# main.net
KiCad netlist of a schematic drawn in Altium Designer
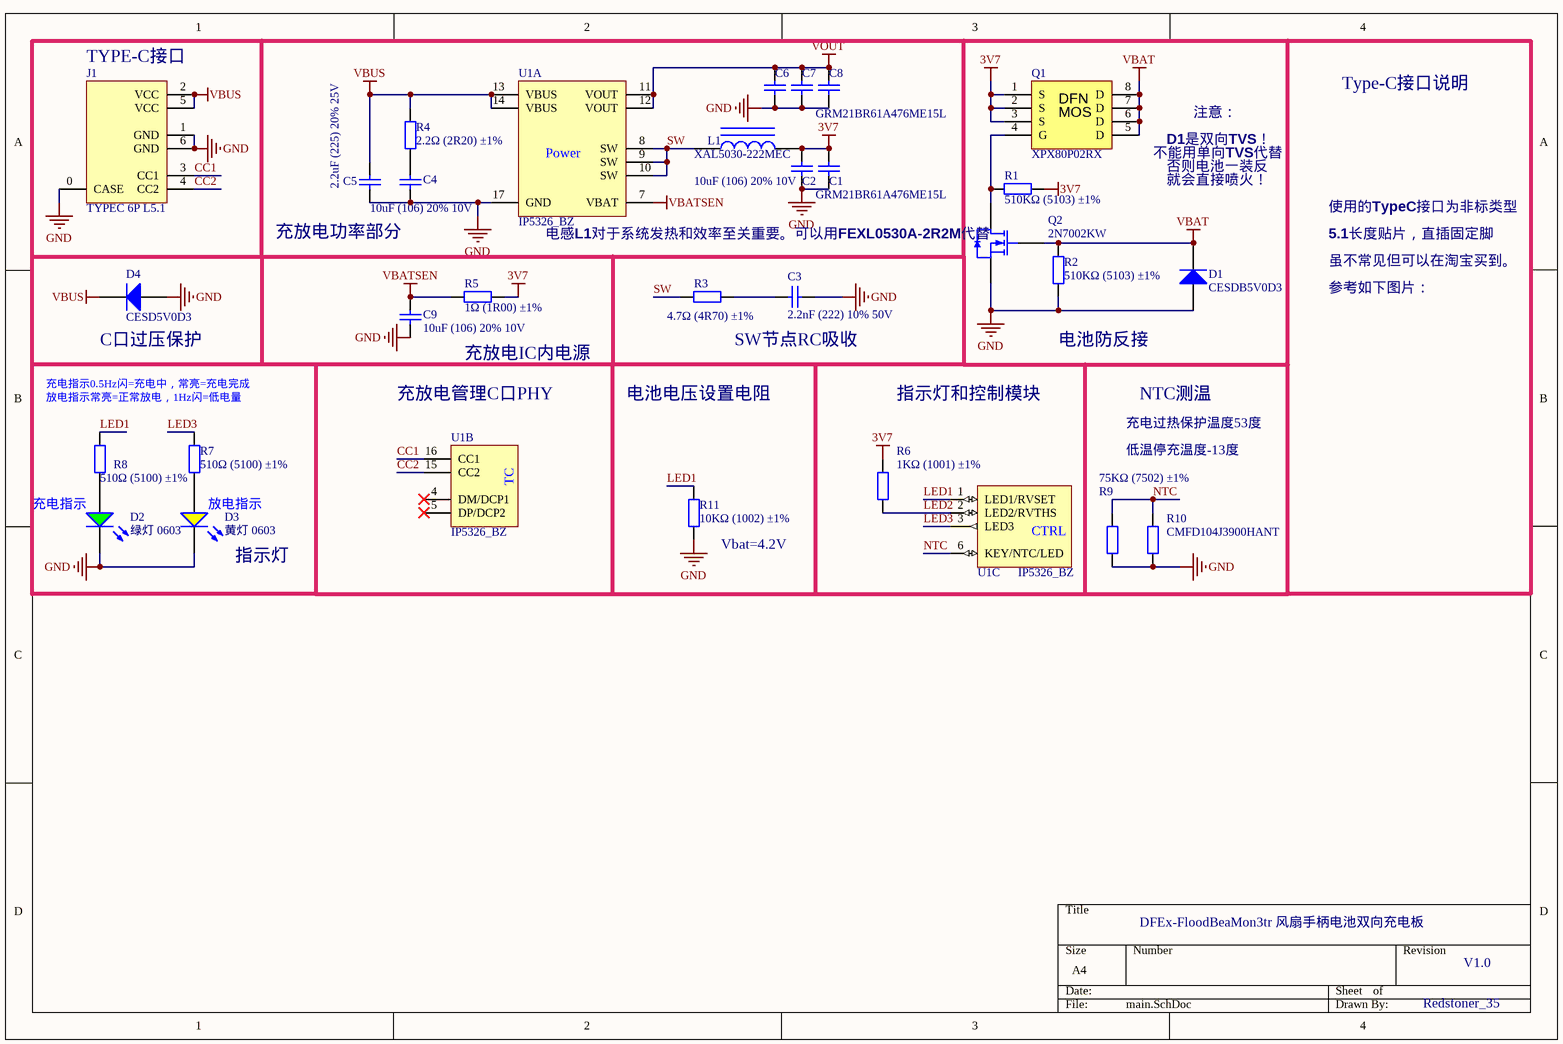
[diagram p0: main.SchDoc]

(export (version "E")
  (design (tool "Eeschema 10.0.6"))
  (components
    (comp (ref "C1")
      (value "GRM21BR61A476ME15L")
      (footprint "0805_C")
      (description "贴片MLCC电容，47uF (476) 20% 10V")
      (libsource (lib "Miscellaneous Devices LC") (part "0805 22uF (226) 20% 25V"))
    )
    (comp (ref "C2")
      (value "10uF (106) 20% 10V")
      (footprint "0402_C")
      (description "贴片电容")
      (libsource (lib "Miscellaneous Devices LC") (part "0402 10uF (106) 20% 6.3V"))
    )
    (comp (ref "C3")
      (value "2.2nF (222) 10% 50V")
      (footprint "0402_C")
      (description "贴片电容")
      (libsource (lib "Miscellaneous Devices LC") (part "0402 2.2nF (222) 10% 50V"))
    )
    (comp (ref "C4")
      (value "10uF (106) 20% 10V")
      (footprint "0402_C")
      (description "贴片电容")
      (libsource (lib "Miscellaneous Devices LC") (part "0402 10uF (106) 20% 6.3V"))
    )
    (comp (ref "C5")
      (value "2.2uF (225) 20% 25V")
      (footprint "0402_C")
      (description "贴片电容")
      (libsource (lib "Miscellaneous Devices LC") (part "0402 1.0uF (105) 10% 25V"))
    )
    (comp (ref "C6")
      (value "GRM21BR61A476ME15L")
      (footprint "0805_C")
      (description "贴片MLCC电容，47uF (476) 20% 10V")
      (libsource (lib "Miscellaneous Devices LC") (part "0805 22uF (226) 20% 25V"))
    )
    (comp (ref "C7")
      (value "GRM21BR61A476ME15L")
      (footprint "0805_C")
      (description "贴片MLCC电容，47uF (476) 20% 10V")
      (libsource (lib "Miscellaneous Devices LC") (part "0805 22uF (226) 20% 25V"))
    )
    (comp (ref "C8")
      (value "GRM21BR61A476ME15L")
      (footprint "0805_C")
      (description "贴片MLCC电容，47uF (476) 20% 10V")
      (libsource (lib "Miscellaneous Devices LC") (part "0805 22uF (226) 20% 25V"))
    )
    (comp (ref "C9")
      (value "10uF (106) 20% 10V")
      (footprint "0402_C")
      (description "贴片电容")
      (libsource (lib "Miscellaneous Devices LC") (part "0402 10uF (106) 20% 6.3V"))
    )
    (comp (ref "D1")
      (value "CESDB5V0D3")
      (footprint "SOD-323")
      (description "5V额定工作电压，6.2V击穿电压双向TVS管，SOD-323")
      (libsource (lib "Miscellaneous Devices LC") (part "SOD-323 1N4148WS T4"))
    )
    (comp (ref "D2")
      (value "绿灯 0603")
      (footprint "0603_LED_S1")
      (description "发光二极管")
      (libsource (lib "Miscellaneous Devices LC") (part "0603 绿灯"))
    )
    (comp (ref "D3")
      (value "黄灯 0603")
      (footprint "0603_LED_S1")
      (description "发光二极管")
      (libsource (lib "Miscellaneous Devices LC") (part "0603 黄灯"))
    )
    (comp (ref "D4")
      (value "CESD5V0D3")
      (footprint "SOD-323")
      (description "5V额定工作电压，6.2V击穿电压双向TVS管，SOD-323")
      (libsource (lib "Miscellaneous Devices LC") (part "SOD-323 1N4148WS T4"))
    )
    (comp (ref "J1")
      (value "TYPEC 6P L5.1")
      (footprint "TYPEC 6P两脚插板SMT L5.1")
      (description "TYPEC连接器 6P 2脚插板SMT 5.1长度")
      (libsource (lib "custom") (part "TYPEC 6P"))
    )
    (comp (ref "L1")
      (value "XAL5030-222MEC")
      (footprint "FEXL0520A-***M")
      (description "线艺XAL5030一体成型电感 9.2A饱和电流，  13.2mΩ DCR 2.2uH±20%")
      (fields (field (name "PUBLISHER") "Altium Limited"))
      (libsource (lib "Miscellaneous Devices") (part "Inductor Iron"))
    )
    (comp (ref "Q1")
      (value "XPX80P02RX")
      (footprint "DFN-8_L3.0-W3.0-P0.65-BL")
      (description "PDFN3x3 20V 80A 4..0mΩ [P-Ch MOSFET")
      (libsource (lib "custom") (part "SON/DFN5x6 MOS"))
    )
    (comp (ref "Q2")
      (value "2N7002KW")
      (footprint "SC70-3")
      (description "单N沟道MOSFET(场效应管)")
      (libsource (lib "Miscellaneous Devices LC") (part "2N7002 7002"))
    )
    (comp (ref "R1")
      (value "510KΩ (5103) ±1%")
      (footprint "0402_R")
      (description "贴片电阻")
      (libsource (lib "Miscellaneous Devices LC") (part "0402 510KΩ (5103) 1%"))
    )
    (comp (ref "R2")
      (value "510KΩ (5103) ±1%")
      (footprint "0402_R")
      (description "贴片电阻")
      (libsource (lib "") (part "0402 510KΩ (5103) 1%_1"))
    )
    (comp (ref "R3")
      (value "4.7Ω (4R70) ±1%")
      (footprint "0402_R")
      (description "贴片电阻")
      (libsource (lib "Miscellaneous Devices LC") (part "0402 4.7KΩ (4701) 1%"))
    )
    (comp (ref "R4")
      (value "2.2Ω (2R20) ±1%")
      (footprint "0402_R")
      (description "贴片电阻")
      (libsource (lib "") (part "0402 4.7KΩ (4701) 1%_1"))
    )
    (comp (ref "R5")
      (value "1Ω (1R00) ±1%")
      (footprint "0805_R")
      (description "贴片电阻")
      (libsource (lib "Miscellaneous Devices LC") (part "0805 1Ω (1R00) 1%"))
    )
    (comp (ref "R6")
      (value "1KΩ (1001) ±1%")
      (footprint "0402_R")
      (description "贴片电阻")
      (libsource (lib "Miscellaneous Devices LC") (part "0402 1KΩ (1001) 1%"))
    )
    (comp (ref "R7")
      (value "510Ω (5100) ±1%")
      (footprint "0402_R")
      (description "贴片电阻")
      (libsource (lib "Miscellaneous Devices LC") (part "0402 100Ω (1000) 1%"))
    )
    (comp (ref "R8")
      (value "510Ω (5100) ±1%")
      (footprint "0402_R")
      (description "贴片电阻")
      (libsource (lib "Miscellaneous Devices LC") (part "0402 100Ω (1000) 1%"))
    )
    (comp (ref "R9")
      (value "75KΩ (7502) ±1%")
      (footprint "0402_R")
      (description "贴片电阻")
      (libsource (lib "Miscellaneous Devices LC") (part "0402 150KΩ (1503) 1%"))
    )
    (comp (ref "R10")
      (value "CMFD104J3900HANT")
      (footprint "0402_R")
      (description "风华0402贴片NTC热敏电阻 B3900 100K ±5%")
      (libsource (lib "Miscellaneous Devices LC") (part "0402 100KΩ (1003) 1%"))
    )
    (comp (ref "R11")
      (value "10KΩ (1002) ±1%")
      (footprint "0402_R")
      (description "贴片电阻")
      (libsource (lib "Miscellaneous Devices LC") (part "0402 10KΩ (1002) 1%"))
    )
    (comp (ref "U1")
      (value "IP5326_BZ")
      (footprint "QFN33-16L-IP5326")
      (description "集成TYPC-C协议的2.4A 5V充放电移动电源SoC QFN3*3封装")
      (libsource (lib "custom") (part "IP5326_BZ"))
    )
  )
  (nets
    (net (code "1") (name "/CC1") (class "Default")
      (node (ref "J1") (pin "3") (pinfunction "CC1_3") (pintype "passive"))
      (node (ref "U1") (pin "16") (pinfunction "CC1_16") (pintype "passive"))
    )
    (net (code "2") (name "/CC2") (class "Default")
      (node (ref "J1") (pin "4") (pinfunction "CC2_4") (pintype "passive"))
      (node (ref "U1") (pin "15") (pinfunction "CC2_15") (pintype "passive"))
    )
    (net (code "3") (name "/LED1") (class "Default")
      (node (ref "R11") (pin "2") (pinfunction "2_2") (pintype "passive"))
      (node (ref "R8") (pin "2") (pinfunction "2_2") (pintype "passive"))
      (node (ref "U1") (pin "1") (pinfunction "LED1/RVSET_1") (pintype "bidirectional"))
    )
    (net (code "4") (name "/LED2") (class "Default")
      (node (ref "R6") (pin "2") (pinfunction "2_2") (pintype "passive"))
      (node (ref "U1") (pin "2") (pinfunction "LED2/RVTHS_2") (pintype "bidirectional"))
    )
    (net (code "5") (name "/LED3") (class "Default")
      (node (ref "R7") (pin "2") (pinfunction "2_2") (pintype "passive"))
      (node (ref "U1") (pin "3") (pinfunction "LED3_3") (pintype "output"))
    )
    (net (code "6") (name "/NTC") (class "Default")
      (node (ref "R10") (pin "2") (pinfunction "2_2") (pintype "passive"))
      (node (ref "R9") (pin "2") (pinfunction "2_2") (pintype "passive"))
      (node (ref "U1") (pin "6") (pinfunction "KEY/NTC/LED_6") (pintype "bidirectional"))
    )
    (net (code "7") (name "/SW") (class "Default")
      (node (ref "L1") (pin "1") (pinfunction "1_1") (pintype "passive"))
      (node (ref "R3") (pin "2") (pinfunction "2_2") (pintype "passive"))
      (node (ref "U1") (pin "10") (pinfunction "SW_10") (pintype "power_in"))
      (node (ref "U1") (pin "8") (pinfunction "SW_8") (pintype "power_in"))
      (node (ref "U1") (pin "9") (pinfunction "SW_9") (pintype "power_in"))
    )
    (net (code "8") (name "3V7") (class "Default")
      (node (ref "C1") (pin "2") (pinfunction "2_2") (pintype "passive"))
      (node (ref "C2") (pin "2") (pinfunction "2_2") (pintype "passive"))
      (node (ref "L1") (pin "2") (pinfunction "2_2") (pintype "passive"))
      (node (ref "Q1") (pin "1") (pinfunction "S_1") (pintype "passive"))
      (node (ref "Q1") (pin "2") (pinfunction "S_2") (pintype "passive"))
      (node (ref "Q1") (pin "3") (pinfunction "S_3") (pintype "passive"))
      (node (ref "R1") (pin "1") (pinfunction "1_1") (pintype "passive"))
      (node (ref "R5") (pin "2") (pinfunction "2_2") (pintype "passive"))
      (node (ref "R6") (pin "1") (pinfunction "1_1") (pintype "passive"))
    )
    (net (code "9") (name "GND") (class "Default")
      (node (ref "C1") (pin "1") (pinfunction "1_1") (pintype "passive"))
      (node (ref "C2") (pin "1") (pinfunction "1_1") (pintype "passive"))
      (node (ref "C3") (pin "1") (pinfunction "1_1") (pintype "passive"))
      (node (ref "C4") (pin "1") (pinfunction "1_1") (pintype "passive"))
      (node (ref "C5") (pin "1") (pinfunction "1_1") (pintype "passive"))
      (node (ref "C6") (pin "1") (pinfunction "1_1") (pintype "passive"))
      (node (ref "C7") (pin "1") (pinfunction "1_1") (pintype "passive"))
      (node (ref "C8") (pin "1") (pinfunction "1_1") (pintype "passive"))
      (node (ref "C9") (pin "1") (pinfunction "1_1") (pintype "passive"))
      (node (ref "D1") (pin "1") (pinfunction "A_1") (pintype "passive"))
      (node (ref "D2") (pin "K") (pinfunction "K_K") (pintype "passive"))
      (node (ref "D3") (pin "K") (pinfunction "K_K") (pintype "passive"))
      (node (ref "D4") (pin "1") (pinfunction "A_1") (pintype "passive"))
      (node (ref "J1") (pin "0") (pinfunction "CASE_0") (pintype "passive"))
      (node (ref "J1") (pin "1") (pinfunction "GND_1") (pintype "power_in"))
      (node (ref "J1") (pin "6") (pinfunction "GND_6") (pintype "power_in"))
      (node (ref "Q2") (pin "2") (pinfunction "S_2") (pintype "passive"))
      (node (ref "R10") (pin "1") (pinfunction "1_1") (pintype "passive"))
      (node (ref "R11") (pin "1") (pinfunction "1_1") (pintype "passive"))
      (node (ref "R2") (pin "1") (pinfunction "1_1") (pintype "passive"))
      (node (ref "R9") (pin "1") (pinfunction "1_1") (pintype "passive"))
      (node (ref "U1") (pin "17") (pinfunction "GND_17") (pintype "power_in"))
    )
    (net (code "10") (name "Net-(C3-Pad2)") (class "Default")
      (node (ref "C3") (pin "2") (pinfunction "2_2") (pintype "passive"))
      (node (ref "R3") (pin "1") (pinfunction "1_1") (pintype "passive"))
    )
    (net (code "11") (name "Net-(C4-Pad2)") (class "Default")
      (node (ref "C4") (pin "2") (pinfunction "2_2") (pintype "passive"))
      (node (ref "R4") (pin "1") (pinfunction "1_1") (pintype "passive"))
    )
    (net (code "12") (name "Net-(D2-PadA)") (class "Default")
      (node (ref "D2") (pin "A") (pinfunction "A_A") (pintype "passive"))
      (node (ref "R8") (pin "1") (pinfunction "1_1") (pintype "passive"))
    )
    (net (code "13") (name "Net-(D3-PadA)") (class "Default")
      (node (ref "D3") (pin "A") (pinfunction "A_A") (pintype "passive"))
      (node (ref "R7") (pin "1") (pinfunction "1_1") (pintype "passive"))
    )
    (net (code "14") (name "Net-(Q1-G)") (class "Default")
      (node (ref "Q1") (pin "4") (pinfunction "G_4") (pintype "passive"))
      (node (ref "Q2") (pin "3") (pinfunction "D_3") (pintype "passive"))
      (node (ref "R1") (pin "2") (pinfunction "2_2") (pintype "passive"))
    )
    (net (code "15") (name "VBAT") (class "Default")
      (node (ref "D1") (pin "2") (pinfunction "K_2") (pintype "passive"))
      (node (ref "Q1") (pin "5") (pinfunction "D_5") (pintype "passive"))
      (node (ref "Q1") (pin "6") (pinfunction "D_6") (pintype "passive"))
      (node (ref "Q1") (pin "7") (pinfunction "D_7") (pintype "passive"))
      (node (ref "Q1") (pin "8") (pinfunction "D_8") (pintype "passive"))
      (node (ref "Q2") (pin "1") (pinfunction "G_1") (pintype "passive"))
      (node (ref "R2") (pin "2") (pinfunction "2_2") (pintype "passive"))
    )
    (net (code "16") (name "VBATSEN") (class "Default")
      (node (ref "C9") (pin "2") (pinfunction "2_2") (pintype "passive"))
      (node (ref "R5") (pin "1") (pinfunction "1_1") (pintype "passive"))
      (node (ref "U1") (pin "7") (pinfunction "VBAT_7") (pintype "power_in"))
    )
    (net (code "17") (name "VBUS") (class "Default")
      (node (ref "C5") (pin "2") (pinfunction "2_2") (pintype "passive"))
      (node (ref "D4") (pin "2") (pinfunction "K_2") (pintype "passive"))
      (node (ref "J1") (pin "2") (pinfunction "VCC_2") (pintype "power_in"))
      (node (ref "J1") (pin "5") (pinfunction "VCC_5") (pintype "power_in"))
      (node (ref "R4") (pin "2") (pinfunction "2_2") (pintype "passive"))
      (node (ref "U1") (pin "13") (pinfunction "VBUS_13") (pintype "power_in"))
      (node (ref "U1") (pin "14") (pinfunction "VBUS_14") (pintype "power_in"))
    )
    (net (code "18") (name "VOUT") (class "Default")
      (node (ref "C6") (pin "2") (pinfunction "2_2") (pintype "passive"))
      (node (ref "C7") (pin "2") (pinfunction "2_2") (pintype "passive"))
      (node (ref "C8") (pin "2") (pinfunction "2_2") (pintype "passive"))
      (node (ref "U1") (pin "11") (pinfunction "VOUT_11") (pintype "power_in"))
      (node (ref "U1") (pin "12") (pinfunction "VOUT_12") (pintype "power_in"))
    )
    (net (code "19") (name "unconnected-(U1B-DM{slash}DCP1-Pad4)") (class "Default")
      (node (ref "U1") (pin "4") (pinfunction "DM/DCP1_4") (pintype "passive+no_connect"))
    )
    (net (code "20") (name "unconnected-(U1B-DP{slash}DCP2-Pad5)") (class "Default")
      (node (ref "U1") (pin "5") (pinfunction "DP/DCP2_5") (pintype "passive+no_connect"))
    )
  )
)
